# 21_CAN.net
KiCad netlist of a schematic drawn in Altium Designer
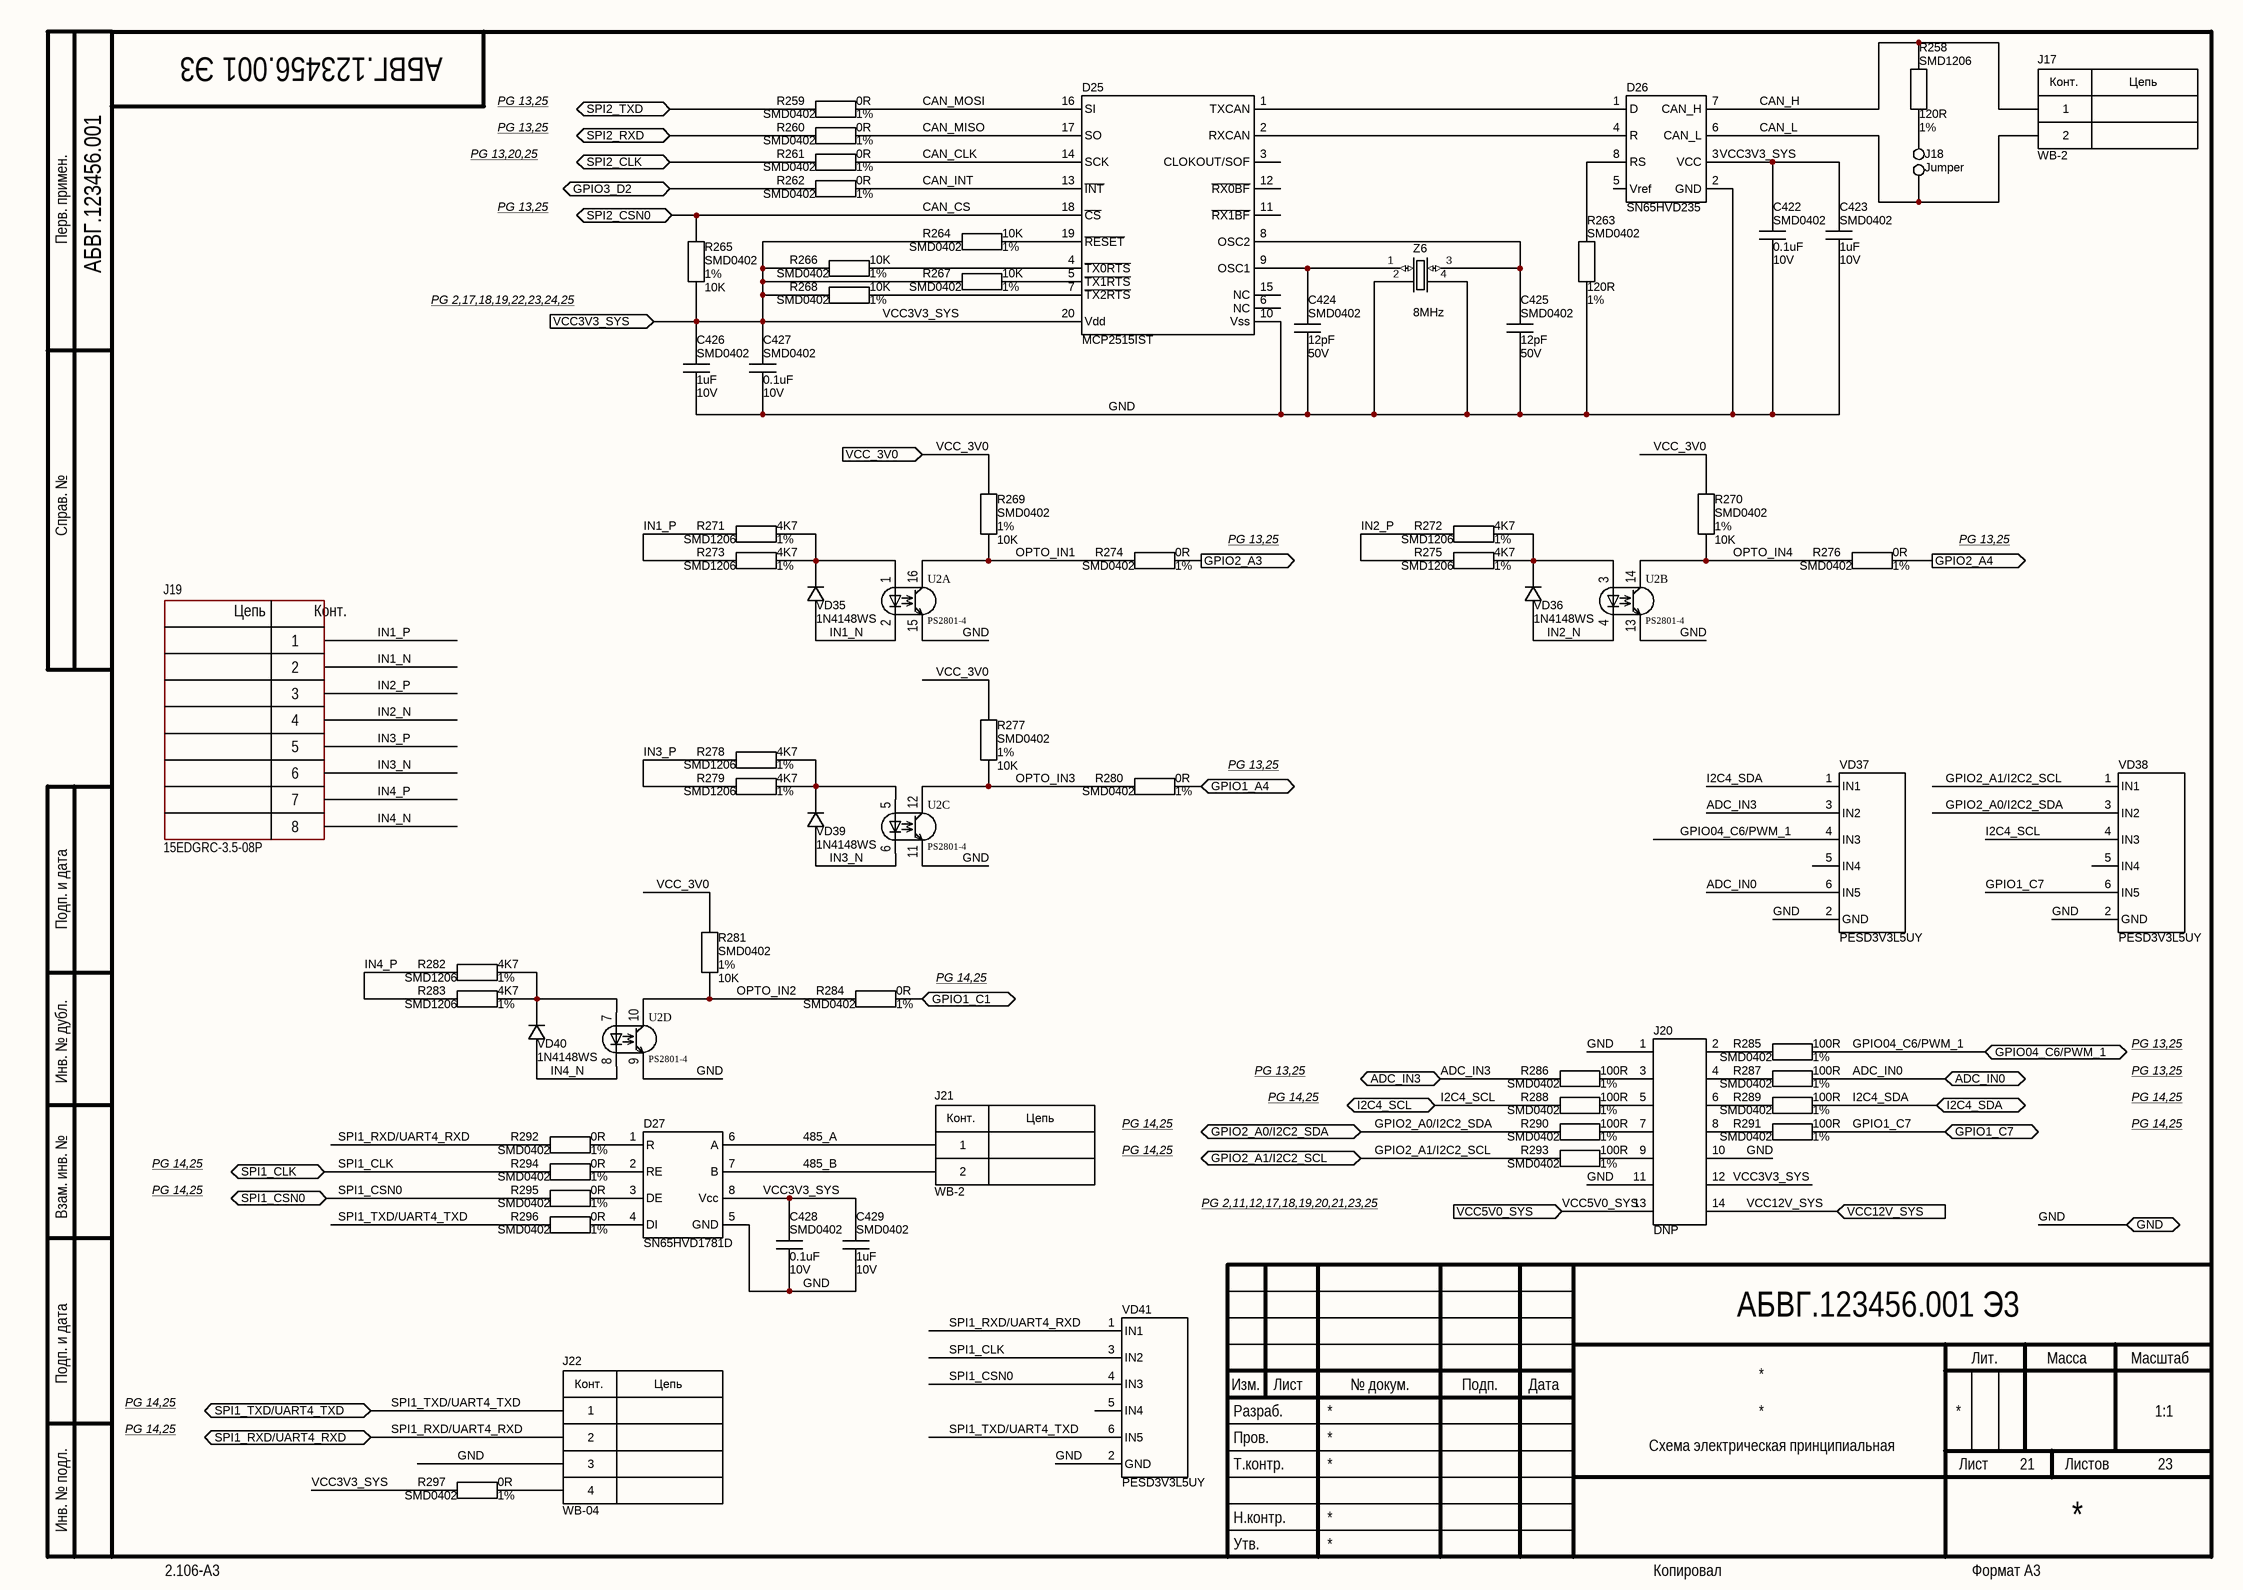
[diagram p0: 21 CAN.SchDoc]

(export (version "E")
  (design (tool "Eeschema 10.0.6"))
  (components
    (comp (ref "C422")
      (value "0.1uF")
      (footprint "Didur_PcbLib_1:CAP_SMD_0402")
      (fields
        (field (name "PACKAGE") "SMD0402")
        (field (name "PARTNUMBER") "CC0402KRX5R6BB104")
        (field (name "VOLTAGE") "10V")
      )
      (libsource (lib "Didur_SchLib_1") (part "Ceramic_Cap"))
    )
    (comp (ref "C423")
      (value "1uF")
      (footprint "Didur_PcbLib_1:CAP_SMD_0402")
      (fields
        (field (name "PACKAGE") "SMD0402")
        (field (name "PARTNUMBER") "CC0402KRX5R6BB105")
        (field (name "VOLTAGE") "10V")
      )
      (libsource (lib "Didur_SchLib_1") (part "Ceramic_Cap"))
    )
    (comp (ref "C424")
      (value "12pF")
      (footprint "Didur_PcbLib_1:CAP_SMD_0402")
      (fields
        (field (name "PACKAGE") "SMD0402")
        (field (name "PARTNUMBER") "CC0402JRNPO9BN120")
        (field (name "VOLTAGE") "50V")
      )
      (libsource (lib "Didur_SchLib_1") (part "Ceramic_Cap"))
    )
    (comp (ref "C425")
      (value "12pF")
      (footprint "Didur_PcbLib_1:CAP_SMD_0402")
      (fields
        (field (name "PACKAGE") "SMD0402")
        (field (name "PARTNUMBER") "CC0402JRNPO9BN120")
        (field (name "VOLTAGE") "50V")
      )
      (libsource (lib "Didur_SchLib_1") (part "Ceramic_Cap"))
    )
    (comp (ref "C426")
      (value "1uF")
      (footprint "Didur_PcbLib_1:CAP_SMD_0402")
      (fields
        (field (name "PACKAGE") "SMD0402")
        (field (name "PARTNUMBER") "CC0402KRX5R6BB105")
        (field (name "VOLTAGE") "10V")
      )
      (libsource (lib "Didur_SchLib_1") (part "Ceramic_Cap"))
    )
    (comp (ref "C427")
      (value "0.1uF")
      (footprint "Didur_PcbLib_1:CAP_SMD_0402")
      (fields
        (field (name "PACKAGE") "SMD0402")
        (field (name "PARTNUMBER") "CC0402KRX5R6BB104")
        (field (name "VOLTAGE") "10V")
      )
      (libsource (lib "Didur_SchLib_1") (part "Ceramic_Cap"))
    )
    (comp (ref "C428")
      (value "0.1uF")
      (footprint "Didur_PcbLib_1:CAP_SMD_0402")
      (fields
        (field (name "PACKAGE") "SMD0402")
        (field (name "PARTNUMBER") "CC0402KRX5R6BB104")
        (field (name "VOLTAGE") "10V")
      )
      (libsource (lib "Didur_SchLib_1") (part "Ceramic_Cap"))
    )
    (comp (ref "C429")
      (value "1uF")
      (footprint "Didur_PcbLib_1:CAP_SMD_0402")
      (fields
        (field (name "PACKAGE") "SMD0402")
        (field (name "PARTNUMBER") "CC0402KRX5R6BB105")
        (field (name "VOLTAGE") "10V")
      )
      (libsource (lib "Didur_SchLib_1") (part "Ceramic_Cap"))
    )
    (comp (ref "D25")
      (value "MCP2515IST")
      (footprint "Didur_PcbLib_1:TSSOP-20")
      (libsource (lib "Didur_SchLib_1") (part "MCP2515IST"))
    )
    (comp (ref "D26")
      (value "SN65HVD235")
      (footprint "SO8")
      (fields (field (name "PARTNUMBER") "SN65HVD235D"))
      (libsource (lib "Didur_SchLib_1") (part "SN65HVD230D"))
    )
    (comp (ref "D27")
      (value "SN65HVD1781D")
      (footprint "SO8")
      (libsource (lib "Didur_SchLib_1") (part "SN65HVD1781D"))
    )
    (comp (ref "J17")
      (value "WB-2")
      (footprint "Didur_PcbLib_1:15EDGRC-3.5-02P")
      (fields (field (name "PARTNUMBER") "DS1066-02M(MW-2M)"))
      (libsource (lib "Didur_SchLib_1") (part "CON2"))
    )
    (comp (ref "J18")
      (value "Jumper")
      (footprint "Didur_PcbLib_1:Jumper2")
      (fields (field (name "PARTNUMBER") "DS1025-01-1x2P8BV1-B"))
      (libsource (lib "Didur_SchLib_1") (part "Jumper"))
    )
    (comp (ref "J19")
      (value "15EDGRC-3.5-08P")
      (footprint "Didur_PcbLib_1:15EDGRC-3.5-08P")
      (libsource (lib "Didur_SchLib_1") (part "CON8"))
    )
    (comp (ref "J20")
      (value "DNP")
      (footprint "Didur_PcbLib_1:PLD2-14 (2.00)")
      (fields (field (name "PARTNUMBER") "PLD2-14 (2.00"))
      (libsource (lib "Didur_SchLib_1") (part "CON14_2"))
    )
    (comp (ref "J21")
      (value "WB-2")
      (footprint "Didur_PcbLib_1:15EDGRC-3.5-02P")
      (fields (field (name "PARTNUMBER") "DS1066-02M(MW-2M)"))
      (libsource (lib "Didur_SchLib_1") (part "CON2"))
    )
    (comp (ref "J22")
      (value "WB-04")
      (footprint "Didur_PcbLib_1:WB-4")
      (fields (field (name "PARTNUMBER") "DS1066-04M"))
      (libsource (lib "Didur_SchLib_1") (part "CON4"))
    )
    (comp (ref "R258")
      (value "120R")
      (footprint "RES_SMD_1206")
      (fields
        (field (name "PACKAGE") "SMD1206")
        (field (name "PARTNUMBER") "RC1206FR-07120RL")
        (field (name "TOLERANCE") "1%")
      )
      (libsource (lib "") (part "Chip_Res_1"))
    )
    (comp (ref "R259")
      (value "0R")
      (footprint "Didur_PcbLib_1:RES_SMD_0402")
      (fields
        (field (name "PACKAGE") "SMD0402")
        (field (name "PARTNUMBER") "RC0402FR-070RL")
        (field (name "TOLERANCE") "1%")
      )
      (libsource (lib "Didur_SchLib_1") (part "Chip_Res"))
    )
    (comp (ref "R260")
      (value "0R")
      (footprint "Didur_PcbLib_1:RES_SMD_0402")
      (fields
        (field (name "PACKAGE") "SMD0402")
        (field (name "PARTNUMBER") "RC0402FR-070RL")
        (field (name "TOLERANCE") "1%")
      )
      (libsource (lib "Didur_SchLib_1") (part "Chip_Res"))
    )
    (comp (ref "R261")
      (value "0R")
      (footprint "Didur_PcbLib_1:RES_SMD_0402")
      (fields
        (field (name "PACKAGE") "SMD0402")
        (field (name "PARTNUMBER") "RC0402FR-070RL")
        (field (name "TOLERANCE") "1%")
      )
      (libsource (lib "Didur_SchLib_1") (part "Chip_Res"))
    )
    (comp (ref "R262")
      (value "0R")
      (footprint "Didur_PcbLib_1:RES_SMD_0402")
      (fields
        (field (name "PACKAGE") "SMD0402")
        (field (name "PARTNUMBER") "RC0402FR-070RL")
        (field (name "TOLERANCE") "1%")
      )
      (libsource (lib "Didur_SchLib_1") (part "Chip_Res"))
    )
    (comp (ref "R263")
      (value "120R")
      (footprint "Didur_PcbLib_1:RES_SMD_0402")
      (fields
        (field (name "PACKAGE") "SMD0402")
        (field (name "PARTNUMBER") "RC0402FR-07120RL")
        (field (name "TOLERANCE") "1%")
      )
      (libsource (lib "") (part "Chip_Res_1"))
    )
    (comp (ref "R264")
      (value "10K")
      (footprint "Didur_PcbLib_1:RES_SMD_0402")
      (fields
        (field (name "PACKAGE") "SMD0402")
        (field (name "PARTNUMBER") "RC0402FR-0710KL")
        (field (name "TOLERANCE") "1%")
      )
      (libsource (lib "") (part "Chip_Res_2"))
    )
    (comp (ref "R265")
      (value "10K")
      (footprint "Didur_PcbLib_1:RES_SMD_0402")
      (fields
        (field (name "PACKAGE") "SMD0402")
        (field (name "PARTNUMBER") "RC0402FR-0710KL")
        (field (name "TOLERANCE") "1%")
      )
      (libsource (lib "") (part "Chip_Res_3"))
    )
    (comp (ref "R266")
      (value "10K")
      (footprint "Didur_PcbLib_1:RES_SMD_0402")
      (fields
        (field (name "PACKAGE") "SMD0402")
        (field (name "PARTNUMBER") "RC0402FR-0710KL")
        (field (name "TOLERANCE") "1%")
      )
      (libsource (lib "") (part "Chip_Res_2"))
    )
    (comp (ref "R267")
      (value "10K")
      (footprint "Didur_PcbLib_1:RES_SMD_0402")
      (fields
        (field (name "PACKAGE") "SMD0402")
        (field (name "PARTNUMBER") "RC0402FR-0710KL")
        (field (name "TOLERANCE") "1%")
      )
      (libsource (lib "") (part "Chip_Res_2"))
    )
    (comp (ref "R268")
      (value "10K")
      (footprint "Didur_PcbLib_1:RES_SMD_0402")
      (fields
        (field (name "PACKAGE") "SMD0402")
        (field (name "PARTNUMBER") "RC0402FR-0710KL")
        (field (name "TOLERANCE") "1%")
      )
      (libsource (lib "") (part "Chip_Res_2"))
    )
    (comp (ref "R269")
      (value "10K")
      (footprint "Didur_PcbLib_1:RES_SMD_0402")
      (fields
        (field (name "PACKAGE") "SMD0402")
        (field (name "PARTNUMBER") "RC0402FR-0710KL")
        (field (name "TOLERANCE") "1%")
      )
      (libsource (lib "") (part "Chip_Res_3"))
    )
    (comp (ref "R270")
      (value "10K")
      (footprint "Didur_PcbLib_1:RES_SMD_0402")
      (fields
        (field (name "PACKAGE") "SMD0402")
        (field (name "PARTNUMBER") "RC0402FR-0710KL")
        (field (name "TOLERANCE") "1%")
      )
      (libsource (lib "") (part "Chip_Res_3"))
    )
    (comp (ref "R271")
      (value "4K7")
      (footprint "RES_SMD_1206")
      (fields
        (field (name "PACKAGE") "SMD1206")
        (field (name "PARTNUMBER") "RC1206FR-074K7L")
        (field (name "TOLERANCE") "1%")
      )
      (libsource (lib "") (part "Chip_Res_2"))
    )
    (comp (ref "R272")
      (value "4K7")
      (footprint "RES_SMD_1206")
      (fields
        (field (name "PACKAGE") "SMD1206")
        (field (name "PARTNUMBER") "RC1206FR-074K7L")
        (field (name "TOLERANCE") "1%")
      )
      (libsource (lib "") (part "Chip_Res_2"))
    )
    (comp (ref "R273")
      (value "4K7")
      (footprint "RES_SMD_1206")
      (fields
        (field (name "PACKAGE") "SMD1206")
        (field (name "PARTNUMBER") "RC1206FR-074K7L")
        (field (name "TOLERANCE") "1%")
      )
      (libsource (lib "") (part "Chip_Res_2"))
    )
    (comp (ref "R274")
      (value "0R")
      (footprint "Didur_PcbLib_1:RES_SMD_0402")
      (fields
        (field (name "PACKAGE") "SMD0402")
        (field (name "PARTNUMBER") "RC0402FR-070RL")
        (field (name "TOLERANCE") "1%")
      )
      (libsource (lib "Didur_SchLib_1") (part "Chip_Res"))
    )
    (comp (ref "R275")
      (value "4K7")
      (footprint "RES_SMD_1206")
      (fields
        (field (name "PACKAGE") "SMD1206")
        (field (name "PARTNUMBER") "RC1206FR-074K7L")
        (field (name "TOLERANCE") "1%")
      )
      (libsource (lib "") (part "Chip_Res_2"))
    )
    (comp (ref "R276")
      (value "0R")
      (footprint "Didur_PcbLib_1:RES_SMD_0402")
      (fields
        (field (name "PACKAGE") "SMD0402")
        (field (name "PARTNUMBER") "RC0402FR-070RL")
        (field (name "TOLERANCE") "1%")
      )
      (libsource (lib "Didur_SchLib_1") (part "Chip_Res"))
    )
    (comp (ref "R277")
      (value "10K")
      (footprint "Didur_PcbLib_1:RES_SMD_0402")
      (fields
        (field (name "PACKAGE") "SMD0402")
        (field (name "PARTNUMBER") "RC0402FR-0710KL")
        (field (name "TOLERANCE") "1%")
      )
      (libsource (lib "") (part "Chip_Res_3"))
    )
    (comp (ref "R278")
      (value "4K7")
      (footprint "RES_SMD_1206")
      (fields
        (field (name "PACKAGE") "SMD1206")
        (field (name "PARTNUMBER") "RC1206FR-074K7L")
        (field (name "TOLERANCE") "1%")
      )
      (libsource (lib "") (part "Chip_Res_2"))
    )
    (comp (ref "R279")
      (value "4K7")
      (footprint "RES_SMD_1206")
      (fields
        (field (name "PACKAGE") "SMD1206")
        (field (name "PARTNUMBER") "RC1206FR-074K7L")
        (field (name "TOLERANCE") "1%")
      )
      (libsource (lib "") (part "Chip_Res_2"))
    )
    (comp (ref "R280")
      (value "0R")
      (footprint "Didur_PcbLib_1:RES_SMD_0402")
      (fields
        (field (name "PACKAGE") "SMD0402")
        (field (name "PARTNUMBER") "RC0402FR-070RL")
        (field (name "TOLERANCE") "1%")
      )
      (libsource (lib "Didur_SchLib_1") (part "Chip_Res"))
    )
    (comp (ref "R281")
      (value "10K")
      (footprint "Didur_PcbLib_1:RES_SMD_0402")
      (fields
        (field (name "PACKAGE") "SMD0402")
        (field (name "PARTNUMBER") "RC0402FR-0710KL")
        (field (name "TOLERANCE") "1%")
      )
      (libsource (lib "") (part "Chip_Res_3"))
    )
    (comp (ref "R282")
      (value "4K7")
      (footprint "RES_SMD_1206")
      (fields
        (field (name "PACKAGE") "SMD1206")
        (field (name "PARTNUMBER") "RC1206FR-074K7L")
        (field (name "TOLERANCE") "1%")
      )
      (libsource (lib "") (part "Chip_Res_2"))
    )
    (comp (ref "R283")
      (value "4K7")
      (footprint "RES_SMD_1206")
      (fields
        (field (name "PACKAGE") "SMD1206")
        (field (name "PARTNUMBER") "RC1206FR-074K7L")
        (field (name "TOLERANCE") "1%")
      )
      (libsource (lib "") (part "Chip_Res_2"))
    )
    (comp (ref "R284")
      (value "0R")
      (footprint "Didur_PcbLib_1:RES_SMD_0402")
      (fields
        (field (name "PACKAGE") "SMD0402")
        (field (name "PARTNUMBER") "RC0402FR-070RL")
        (field (name "TOLERANCE") "1%")
      )
      (libsource (lib "Didur_SchLib_1") (part "Chip_Res"))
    )
    (comp (ref "R285")
      (value "100R")
      (footprint "Didur_PcbLib_1:RES_SMD_0402")
      (fields
        (field (name "PACKAGE") "SMD0402")
        (field (name "PARTNUMBER") "RC0402FR-07100RL")
        (field (name "TOLERANCE") "1%")
      )
      (libsource (lib "Didur_SchLib_1") (part "Chip_Res"))
    )
    (comp (ref "R286")
      (value "100R")
      (footprint "Didur_PcbLib_1:RES_SMD_0402")
      (fields
        (field (name "PACKAGE") "SMD0402")
        (field (name "PARTNUMBER") "RC0402FR-07100RL")
        (field (name "TOLERANCE") "1%")
      )
      (libsource (lib "Didur_SchLib_1") (part "Chip_Res"))
    )
    (comp (ref "R287")
      (value "100R")
      (footprint "Didur_PcbLib_1:RES_SMD_0402")
      (fields
        (field (name "PACKAGE") "SMD0402")
        (field (name "PARTNUMBER") "RC0402FR-07100RL")
        (field (name "TOLERANCE") "1%")
      )
      (libsource (lib "Didur_SchLib_1") (part "Chip_Res"))
    )
    (comp (ref "R288")
      (value "100R")
      (footprint "Didur_PcbLib_1:RES_SMD_0402")
      (fields
        (field (name "PACKAGE") "SMD0402")
        (field (name "PARTNUMBER") "RC0402FR-07100RL")
        (field (name "TOLERANCE") "1%")
      )
      (libsource (lib "Didur_SchLib_1") (part "Chip_Res"))
    )
    (comp (ref "R289")
      (value "100R")
      (footprint "Didur_PcbLib_1:RES_SMD_0402")
      (fields
        (field (name "PACKAGE") "SMD0402")
        (field (name "PARTNUMBER") "RC0402FR-07100RL")
        (field (name "TOLERANCE") "1%")
      )
      (libsource (lib "Didur_SchLib_1") (part "Chip_Res"))
    )
    (comp (ref "R290")
      (value "100R")
      (footprint "Didur_PcbLib_1:RES_SMD_0402")
      (fields
        (field (name "PACKAGE") "SMD0402")
        (field (name "PARTNUMBER") "RC0402FR-07100RL")
        (field (name "TOLERANCE") "1%")
      )
      (libsource (lib "Didur_SchLib_1") (part "Chip_Res"))
    )
    (comp (ref "R291")
      (value "100R")
      (footprint "Didur_PcbLib_1:RES_SMD_0402")
      (fields
        (field (name "PACKAGE") "SMD0402")
        (field (name "PARTNUMBER") "RC0402FR-07100RL")
        (field (name "TOLERANCE") "1%")
      )
      (libsource (lib "Didur_SchLib_1") (part "Chip_Res"))
    )
    (comp (ref "R292")
      (value "0R")
      (footprint "Didur_PcbLib_1:RES_SMD_0402")
      (fields
        (field (name "PACKAGE") "SMD0402")
        (field (name "PARTNUMBER") "RC0402FR-070RL")
        (field (name "TOLERANCE") "1%")
      )
      (libsource (lib "Didur_SchLib_1") (part "Chip_Res"))
    )
    (comp (ref "R293")
      (value "100R")
      (footprint "Didur_PcbLib_1:RES_SMD_0402")
      (fields
        (field (name "PACKAGE") "SMD0402")
        (field (name "PARTNUMBER") "RC0402FR-07100RL")
        (field (name "TOLERANCE") "1%")
      )
      (libsource (lib "Didur_SchLib_1") (part "Chip_Res"))
    )
    (comp (ref "R294")
      (value "0R")
      (footprint "Didur_PcbLib_1:RES_SMD_0402")
      (fields
        (field (name "PACKAGE") "SMD0402")
        (field (name "PARTNUMBER") "RC0402FR-070RL")
        (field (name "TOLERANCE") "1%")
      )
      (libsource (lib "Didur_SchLib_1") (part "Chip_Res"))
    )
    (comp (ref "R295")
      (value "0R")
      (footprint "Didur_PcbLib_1:RES_SMD_0402")
      (fields
        (field (name "PACKAGE") "SMD0402")
        (field (name "PARTNUMBER") "RC0402FR-070RL")
        (field (name "TOLERANCE") "1%")
      )
      (libsource (lib "Didur_SchLib_1") (part "Chip_Res"))
    )
    (comp (ref "R296")
      (value "0R")
      (footprint "Didur_PcbLib_1:RES_SMD_0402")
      (fields
        (field (name "PACKAGE") "SMD0402")
        (field (name "PARTNUMBER") "RC0402FR-070RL")
        (field (name "TOLERANCE") "1%")
      )
      (libsource (lib "Didur_SchLib_1") (part "Chip_Res"))
    )
    (comp (ref "R297")
      (value "0R")
      (footprint "Didur_PcbLib_1:RES_SMD_0402")
      (fields
        (field (name "PACKAGE") "SMD0402")
        (field (name "PARTNUMBER") "RC0402FR-070RL")
        (field (name "TOLERANCE") "1%")
      )
      (libsource (lib "Didur_SchLib_1") (part "Chip_Res"))
    )
    (comp (ref "U2")
      (value "PS2801-4")
      (footprint "SOIC127P700X210-16N")
      (description "Optocoupler X4")
      (fields (field (name "MANUFACTURER") "Renesas") (field (name "PARTNUMBER") "PS2801-4-F3-A"))
      (libsource (lib "Didur_SchLib_1") (part "PS2801-4-F3-A"))
    )
    (comp (ref "VD35")
      (value "1N4148WS")
      (footprint "SOD323")
      (fields (field (name "Comment") "Diode"))
      (libsource (lib "Didur_SchLib_1") (part "Diode"))
    )
    (comp (ref "VD36")
      (value "1N4148WS")
      (footprint "SOD323")
      (fields (field (name "Comment") "Diode"))
      (libsource (lib "Didur_SchLib_1") (part "Diode"))
    )
    (comp (ref "VD37")
      (value "PESD3V3L5UY")
      (footprint "Didur_PcbLib_1:SC70-6")
      (libsource (lib "Didur_SchLib_1") (part "PESD3V3L5UY"))
    )
    (comp (ref "VD38")
      (value "PESD3V3L5UY")
      (footprint "Didur_PcbLib_1:SC70-6")
      (libsource (lib "Didur_SchLib_1") (part "PESD3V3L5UY"))
    )
    (comp (ref "VD39")
      (value "1N4148WS")
      (footprint "SOD323")
      (fields (field (name "Comment") "Diode"))
      (libsource (lib "Didur_SchLib_1") (part "Diode"))
    )
    (comp (ref "VD40")
      (value "1N4148WS")
      (footprint "SOD323")
      (fields (field (name "Comment") "Diode"))
      (libsource (lib "Didur_SchLib_1") (part "Diode"))
    )
    (comp (ref "VD41")
      (value "PESD3V3L5UY")
      (footprint "Didur_PcbLib_1:SC70-6")
      (libsource (lib "Didur_SchLib_1") (part "PESD3V3L5UY"))
    )
    (comp (ref "Z6")
      (value "8MHz")
      (footprint "Didur_PcbLib_1:TSX3225")
      (fields (field (name "PARTNUMBER") "X32258MOB4SI") (field (name "Comment") "Value"))
      (libsource (lib "Didur_SchLib_1") (part "OSC3225"))
    )
  )
  (nets
    (net (code "1") (name "/485_A") (class "Default")
      (node (ref "D27") (pin "6") (pinfunction "A_6") (pintype "passive"))
      (node (ref "J21") (pin "1") (pinfunction "1_1") (pintype "passive"))
    )
    (net (code "2") (name "/485_B") (class "Default")
      (node (ref "D27") (pin "7") (pinfunction "B_7") (pintype "passive"))
      (node (ref "J21") (pin "2") (pinfunction "2_2") (pintype "passive"))
    )
    (net (code "3") (name "/ADC_IN0") (class "Default")
      (node (ref "R287") (pin "2") (pinfunction "2_2") (pintype "passive"))
      (node (ref "VD37") (pin "6") (pinfunction "IN5_6") (pintype "passive"))
    )
    (net (code "4") (name "/ADC_IN3") (class "Default")
      (node (ref "R286") (pin "1") (pinfunction "1_1") (pintype "passive"))
      (node (ref "VD37") (pin "3") (pinfunction "IN2_3") (pintype "passive"))
    )
    (net (code "5") (name "/CAN_CLK") (class "Default")
      (node (ref "D25") (pin "14") (pinfunction "SCK_14") (pintype "passive"))
      (node (ref "R261") (pin "2") (pinfunction "2_2") (pintype "passive"))
    )
    (net (code "6") (name "/CAN_CS") (class "Default")
      (node (ref "D25") (pin "18") (pinfunction "~{CS}_18") (pintype "passive"))
      (node (ref "R265") (pin "2") (pinfunction "2_2") (pintype "passive"))
    )
    (net (code "7") (name "/CAN_H") (class "Default")
      (node (ref "D26") (pin "7") (pinfunction "CAN_H_7") (pintype "passive"))
      (node (ref "J17") (pin "1") (pinfunction "1_1") (pintype "passive"))
      (node (ref "R258") (pin "1") (pinfunction "1_1") (pintype "passive"))
    )
    (net (code "8") (name "/CAN_INT") (class "Default")
      (node (ref "D25") (pin "13") (pinfunction "~{INT}_13") (pintype "passive"))
      (node (ref "R262") (pin "2") (pinfunction "2_2") (pintype "passive"))
    )
    (net (code "9") (name "/CAN_L") (class "Default")
      (node (ref "D26") (pin "6") (pinfunction "CAN_L_6") (pintype "passive"))
      (node (ref "J17") (pin "2") (pinfunction "2_2") (pintype "passive"))
      (node (ref "J18") (pin "1") (pinfunction "1_1") (pintype "passive"))
    )
    (net (code "10") (name "/CAN_MISO") (class "Default")
      (node (ref "D25") (pin "17") (pinfunction "SO_17") (pintype "passive"))
      (node (ref "R260") (pin "2") (pinfunction "2_2") (pintype "passive"))
    )
    (net (code "11") (name "/CAN_MOSI") (class "Default")
      (node (ref "D25") (pin "16") (pinfunction "SI_16") (pintype "passive"))
      (node (ref "R259") (pin "2") (pinfunction "2_2") (pintype "passive"))
    )
    (net (code "12") (name "/GND") (class "Default")
      (node (ref "C422") (pin "2") (pinfunction "2_2") (pintype "power_in"))
      (node (ref "C423") (pin "2") (pinfunction "2_2") (pintype "power_in"))
      (node (ref "C424") (pin "2") (pinfunction "2_2") (pintype "power_in"))
      (node (ref "C425") (pin "2") (pinfunction "2_2") (pintype "power_in"))
      (node (ref "C426") (pin "2") (pinfunction "2_2") (pintype "power_in"))
      (node (ref "C427") (pin "2") (pinfunction "2_2") (pintype "power_in"))
      (node (ref "C428") (pin "2") (pinfunction "2_2") (pintype "power_in"))
      (node (ref "C429") (pin "2") (pinfunction "2_2") (pintype "power_in"))
      (node (ref "D25") (pin "10") (pinfunction "Vss_10") (pintype "passive"))
      (node (ref "D26") (pin "2") (pinfunction "GND_2") (pintype "passive"))
      (node (ref "D27") (pin "5") (pinfunction "GND_5") (pintype "passive"))
      (node (ref "J20") (pin "1") (pinfunction "1_1") (pintype "passive"))
      (node (ref "J20") (pin "10") (pinfunction "10_10") (pintype "passive"))
      (node (ref "J20") (pin "11") (pinfunction "11_11") (pintype "passive"))
      (node (ref "J22") (pin "3") (pinfunction "3_3") (pintype "power_in"))
      (node (ref "R263") (pin "2") (pinfunction "2_2") (pintype "passive"))
      (node (ref "U2") (pin "11") (pinfunction "E_11") (pintype "passive"))
      (node (ref "U2") (pin "13") (pinfunction "E_13") (pintype "passive"))
      (node (ref "U2") (pin "15") (pinfunction "E_15") (pintype "passive"))
      (node (ref "U2") (pin "9") (pinfunction "E_9") (pintype "passive"))
      (node (ref "VD37") (pin "2") (pinfunction "GND_2") (pintype "passive"))
      (node (ref "VD38") (pin "2") (pinfunction "GND_2") (pintype "passive"))
      (node (ref "VD41") (pin "2") (pinfunction "GND_2") (pintype "passive"))
      (node (ref "Z6") (pin "2") (pinfunction "GND_2") (pintype "passive"))
      (node (ref "Z6") (pin "4") (pinfunction "GND_4") (pintype "passive"))
    )
    (net (code "13") (name "/GPIO1_A4") (class "Default")
      (node (ref "R280") (pin "2") (pinfunction "2_2") (pintype "passive"))
    )
    (net (code "14") (name "/GPIO1_C1") (class "Default")
      (node (ref "R284") (pin "2") (pinfunction "2_2") (pintype "passive"))
    )
    (net (code "15") (name "/GPIO1_C7") (class "Default")
      (node (ref "R291") (pin "2") (pinfunction "2_2") (pintype "passive"))
      (node (ref "VD38") (pin "6") (pinfunction "IN5_6") (pintype "passive"))
    )
    (net (code "16") (name "/GPIO2_A0{slash}I2C2_SDA") (class "Default")
      (node (ref "R290") (pin "1") (pinfunction "1_1") (pintype "passive"))
      (node (ref "VD38") (pin "3") (pinfunction "IN2_3") (pintype "passive"))
    )
    (net (code "17") (name "/GPIO2_A1{slash}I2C2_SCL") (class "Default")
      (node (ref "R293") (pin "1") (pinfunction "1_1") (pintype "passive"))
      (node (ref "VD38") (pin "1") (pinfunction "IN1_1") (pintype "passive"))
    )
    (net (code "18") (name "/GPIO2_A3") (class "Default")
      (node (ref "R274") (pin "2") (pinfunction "2_2") (pintype "passive"))
    )
    (net (code "19") (name "/GPIO2_A4") (class "Default")
      (node (ref "R276") (pin "2") (pinfunction "2_2") (pintype "passive"))
    )
    (net (code "20") (name "/GPIO3_D2") (class "Default")
      (node (ref "R262") (pin "1") (pinfunction "1_1") (pintype "passive"))
    )
    (net (code "21") (name "/GPIO04_C6{slash}PWM_1") (class "Default")
      (node (ref "R285") (pin "2") (pinfunction "2_2") (pintype "passive"))
      (node (ref "VD37") (pin "4") (pinfunction "IN3_4") (pintype "passive"))
    )
    (net (code "22") (name "/I2C4_SCL") (class "Default")
      (node (ref "R288") (pin "1") (pinfunction "1_1") (pintype "passive"))
      (node (ref "VD38") (pin "4") (pinfunction "IN3_4") (pintype "passive"))
    )
    (net (code "23") (name "/I2C4_SDA") (class "Default")
      (node (ref "R289") (pin "2") (pinfunction "2_2") (pintype "passive"))
      (node (ref "VD37") (pin "1") (pinfunction "IN1_1") (pintype "passive"))
    )
    (net (code "24") (name "/IN1_N") (class "Default")
      (node (ref "J19") (pin "2") (pinfunction "2_2") (pintype "passive"))
      (node (ref "U2") (pin "2") (pinfunction "C_2") (pintype "passive"))
      (node (ref "VD35") (pin "1") (pinfunction "A_1") (pintype "passive"))
    )
    (net (code "25") (name "/IN1_P") (class "Default")
      (node (ref "J19") (pin "1") (pinfunction "1_1") (pintype "passive"))
      (node (ref "R271") (pin "2") (pinfunction "2_2") (pintype "passive"))
      (node (ref "R273") (pin "2") (pinfunction "2_2") (pintype "passive"))
    )
    (net (code "26") (name "/IN2_N") (class "Default")
      (node (ref "J19") (pin "4") (pinfunction "4_4") (pintype "power_in"))
      (node (ref "U2") (pin "4") (pinfunction "C_4") (pintype "passive"))
      (node (ref "VD36") (pin "1") (pinfunction "A_1") (pintype "passive"))
    )
    (net (code "27") (name "/IN2_P") (class "Default")
      (node (ref "J19") (pin "3") (pinfunction "3_3") (pintype "power_in"))
      (node (ref "R272") (pin "2") (pinfunction "2_2") (pintype "passive"))
      (node (ref "R275") (pin "2") (pinfunction "2_2") (pintype "passive"))
    )
    (net (code "28") (name "/IN3_N") (class "Default")
      (node (ref "J19") (pin "6") (pinfunction "6_6") (pintype "power_in"))
      (node (ref "U2") (pin "6") (pinfunction "C_6") (pintype "passive"))
      (node (ref "VD39") (pin "1") (pinfunction "A_1") (pintype "passive"))
    )
    (net (code "29") (name "/IN3_P") (class "Default")
      (node (ref "J19") (pin "5") (pinfunction "5_5") (pintype "power_in"))
      (node (ref "R278") (pin "2") (pinfunction "2_2") (pintype "passive"))
      (node (ref "R279") (pin "2") (pinfunction "2_2") (pintype "passive"))
    )
    (net (code "30") (name "/IN4_N") (class "Default")
      (node (ref "J19") (pin "8") (pinfunction "8_8") (pintype "power_in"))
      (node (ref "U2") (pin "8") (pinfunction "C_8") (pintype "passive"))
      (node (ref "VD40") (pin "1") (pinfunction "A_1") (pintype "passive"))
    )
    (net (code "31") (name "/IN4_P") (class "Default")
      (node (ref "J19") (pin "7") (pinfunction "7_7") (pintype "power_in"))
      (node (ref "R282") (pin "2") (pinfunction "2_2") (pintype "passive"))
      (node (ref "R283") (pin "2") (pinfunction "2_2") (pintype "passive"))
    )
    (net (code "32") (name "/OPTO_IN1") (class "Default")
      (node (ref "R269") (pin "1") (pinfunction "1_1") (pintype "passive"))
      (node (ref "R274") (pin "1") (pinfunction "1_1") (pintype "passive"))
      (node (ref "U2") (pin "16") (pinfunction "C_16") (pintype "passive"))
    )
    (net (code "33") (name "/OPTO_IN2") (class "Default")
      (node (ref "R281") (pin "1") (pinfunction "1_1") (pintype "passive"))
      (node (ref "R284") (pin "1") (pinfunction "1_1") (pintype "passive"))
      (node (ref "U2") (pin "10") (pinfunction "C_10") (pintype "passive"))
    )
    (net (code "34") (name "/OPTO_IN3") (class "Default")
      (node (ref "R277") (pin "1") (pinfunction "1_1") (pintype "passive"))
      (node (ref "R280") (pin "1") (pinfunction "1_1") (pintype "passive"))
      (node (ref "U2") (pin "12") (pinfunction "C_12") (pintype "passive"))
    )
    (net (code "35") (name "/OPTO_IN4") (class "Default")
      (node (ref "R270") (pin "1") (pinfunction "1_1") (pintype "passive"))
      (node (ref "R276") (pin "1") (pinfunction "1_1") (pintype "passive"))
      (node (ref "U2") (pin "14") (pinfunction "C_14") (pintype "passive"))
    )
    (net (code "36") (name "/SPI1_CLK") (class "Default")
      (node (ref "R294") (pin "1") (pinfunction "1_1") (pintype "passive"))
      (node (ref "VD41") (pin "3") (pinfunction "IN2_3") (pintype "passive"))
    )
    (net (code "37") (name "/SPI1_CSN0") (class "Default")
      (node (ref "R295") (pin "1") (pinfunction "1_1") (pintype "passive"))
      (node (ref "VD41") (pin "4") (pinfunction "IN3_4") (pintype "passive"))
    )
    (net (code "38") (name "/SPI1_RXD{slash}UART4_RXD") (class "Default")
      (node (ref "J22") (pin "2") (pinfunction "2_2") (pintype "passive"))
      (node (ref "R292") (pin "1") (pinfunction "1_1") (pintype "passive"))
      (node (ref "VD41") (pin "1") (pinfunction "IN1_1") (pintype "passive"))
    )
    (net (code "39") (name "/SPI1_TXD{slash}UART4_TXD") (class "Default")
      (node (ref "J22") (pin "1") (pinfunction "1_1") (pintype "passive"))
      (node (ref "R296") (pin "1") (pinfunction "1_1") (pintype "passive"))
      (node (ref "VD41") (pin "6") (pinfunction "IN5_6") (pintype "passive"))
    )
    (net (code "40") (name "/SPI2_CLK") (class "Default")
      (node (ref "R261") (pin "1") (pinfunction "1_1") (pintype "passive"))
    )
    (net (code "41") (name "/SPI2_RXD") (class "Default")
      (node (ref "R260") (pin "1") (pinfunction "1_1") (pintype "passive"))
    )
    (net (code "42") (name "/SPI2_TXD") (class "Default")
      (node (ref "R259") (pin "1") (pinfunction "1_1") (pintype "passive"))
    )
    (net (code "43") (name "/VCC3V3_SYS") (class "Default")
      (node (ref "C422") (pin "1") (pinfunction "1_1") (pintype "power_in"))
      (node (ref "C423") (pin "1") (pinfunction "1_1") (pintype "power_in"))
      (node (ref "C426") (pin "1") (pinfunction "1_1") (pintype "power_in"))
      (node (ref "C427") (pin "1") (pinfunction "1_1") (pintype "power_in"))
      (node (ref "C428") (pin "1") (pinfunction "1_1") (pintype "power_in"))
      (node (ref "C429") (pin "1") (pinfunction "1_1") (pintype "power_in"))
      (node (ref "D25") (pin "20") (pinfunction "Vdd_20") (pintype "passive"))
      (node (ref "D26") (pin "3") (pinfunction "VCC_3") (pintype "passive"))
      (node (ref "D27") (pin "8") (pinfunction "Vcc_8") (pintype "passive"))
      (node (ref "J20") (pin "12") (pinfunction "12_12") (pintype "passive"))
      (node (ref "R264") (pin "2") (pinfunction "2_2") (pintype "passive"))
      (node (ref "R265") (pin "1") (pinfunction "1_1") (pintype "passive"))
      (node (ref "R266") (pin "2") (pinfunction "2_2") (pintype "passive"))
      (node (ref "R267") (pin "2") (pinfunction "2_2") (pintype "passive"))
      (node (ref "R268") (pin "2") (pinfunction "2_2") (pintype "passive"))
      (node (ref "R297") (pin "1") (pinfunction "1_1") (pintype "passive"))
    )
    (net (code "44") (name "/VCC5V0_SYS") (class "Default")
      (node (ref "J20") (pin "13") (pinfunction "13_13") (pintype "passive"))
    )
    (net (code "45") (name "/VCC12V_SYS") (class "Default")
      (node (ref "J20") (pin "14") (pinfunction "14_14") (pintype "passive"))
    )
    (net (code "46") (name "/VCC_3V0") (class "Default")
      (node (ref "R269") (pin "2") (pinfunction "2_2") (pintype "passive"))
      (node (ref "R270") (pin "2") (pinfunction "2_2") (pintype "passive"))
      (node (ref "R277") (pin "2") (pinfunction "2_2") (pintype "passive"))
      (node (ref "R281") (pin "2") (pinfunction "2_2") (pintype "passive"))
    )
    (net (code "47") (name "Net-(D25-OSC1)") (class "Default")
      (node (ref "C424") (pin "1") (pinfunction "1_1") (pintype "power_in"))
      (node (ref "D25") (pin "9") (pinfunction "OSC1_9") (pintype "passive"))
      (node (ref "Z6") (pin "1") (pinfunction "IN/OUT_1") (pintype "bidirectional"))
    )
    (net (code "48") (name "Net-(D25-OSC2)") (class "Default")
      (node (ref "C425") (pin "1") (pinfunction "1_1") (pintype "power_in"))
      (node (ref "D25") (pin "8") (pinfunction "OSC2_8") (pintype "passive"))
      (node (ref "Z6") (pin "3") (pinfunction "IN/OUT_3") (pintype "bidirectional"))
    )
    (net (code "49") (name "Net-(D25-RXCAN)") (class "Default")
      (node (ref "D25") (pin "2") (pinfunction "RXCAN_2") (pintype "passive"))
      (node (ref "D26") (pin "4") (pinfunction "R_4") (pintype "passive"))
    )
    (net (code "50") (name "Net-(D25-TXCAN)") (class "Default")
      (node (ref "D25") (pin "1") (pinfunction "TXCAN_1") (pintype "passive"))
      (node (ref "D26") (pin "1") (pinfunction "D_1") (pintype "passive"))
    )
    (net (code "51") (name "Net-(D25-~{RESET})") (class "Default")
      (node (ref "D25") (pin "19") (pinfunction "~{RESET}_19") (pintype "passive"))
      (node (ref "R264") (pin "1") (pinfunction "1_1") (pintype "passive"))
    )
    (net (code "52") (name "Net-(D25-~{TX0RTS})") (class "Default")
      (node (ref "D25") (pin "4") (pinfunction "~{TX0RTS}_4") (pintype "passive"))
      (node (ref "R266") (pin "1") (pinfunction "1_1") (pintype "passive"))
    )
    (net (code "53") (name "Net-(D25-~{TX1RTS})") (class "Default")
      (node (ref "D25") (pin "5") (pinfunction "~{TX1RTS}_5") (pintype "passive"))
      (node (ref "R267") (pin "1") (pinfunction "1_1") (pintype "passive"))
    )
    (net (code "54") (name "Net-(D25-~{TX2RTS})") (class "Default")
      (node (ref "D25") (pin "7") (pinfunction "~{TX2RTS}_7") (pintype "passive"))
      (node (ref "R268") (pin "1") (pinfunction "1_1") (pintype "passive"))
    )
    (net (code "55") (name "Net-(D26-RS)") (class "Default")
      (node (ref "D26") (pin "8") (pinfunction "RS_8") (pintype "passive"))
      (node (ref "R263") (pin "1") (pinfunction "1_1") (pintype "passive"))
    )
    (net (code "56") (name "Net-(D27-DE)") (class "Default")
      (node (ref "D27") (pin "3") (pinfunction "DE_3") (pintype "passive"))
      (node (ref "R295") (pin "2") (pinfunction "2_2") (pintype "passive"))
    )
    (net (code "57") (name "Net-(D27-DI)") (class "Default")
      (node (ref "D27") (pin "4") (pinfunction "DI_4") (pintype "passive"))
      (node (ref "R296") (pin "2") (pinfunction "2_2") (pintype "passive"))
    )
    (net (code "58") (name "Net-(D27-R)") (class "Default")
      (node (ref "D27") (pin "1") (pinfunction "R_1") (pintype "passive"))
      (node (ref "R292") (pin "2") (pinfunction "2_2") (pintype "passive"))
    )
    (net (code "59") (name "Net-(D27-RE)") (class "Default")
      (node (ref "D27") (pin "2") (pinfunction "RE_2") (pintype "passive"))
      (node (ref "R294") (pin "2") (pinfunction "2_2") (pintype "passive"))
    )
    (net (code "60") (name "Net-(J18-Pad2)") (class "Default")
      (node (ref "J18") (pin "2") (pinfunction "2_2") (pintype "passive"))
      (node (ref "R258") (pin "2") (pinfunction "2_2") (pintype "passive"))
    )
    (net (code "61") (name "Net-(J20-Pad2)") (class "Default")
      (node (ref "J20") (pin "2") (pinfunction "2_2") (pintype "passive"))
      (node (ref "R285") (pin "1") (pinfunction "1_1") (pintype "passive"))
    )
    (net (code "62") (name "Net-(J20-Pad3)") (class "Default")
      (node (ref "J20") (pin "3") (pinfunction "3_3") (pintype "passive"))
      (node (ref "R286") (pin "2") (pinfunction "2_2") (pintype "passive"))
    )
    (net (code "63") (name "Net-(J20-Pad4)") (class "Default")
      (node (ref "J20") (pin "4") (pinfunction "4_4") (pintype "passive"))
      (node (ref "R287") (pin "1") (pinfunction "1_1") (pintype "passive"))
    )
    (net (code "64") (name "Net-(J20-Pad5)") (class "Default")
      (node (ref "J20") (pin "5") (pinfunction "5_5") (pintype "passive"))
      (node (ref "R288") (pin "2") (pinfunction "2_2") (pintype "passive"))
    )
    (net (code "65") (name "Net-(J20-Pad6)") (class "Default")
      (node (ref "J20") (pin "6") (pinfunction "6_6") (pintype "passive"))
      (node (ref "R289") (pin "1") (pinfunction "1_1") (pintype "passive"))
    )
    (net (code "66") (name "Net-(J20-Pad7)") (class "Default")
      (node (ref "J20") (pin "7") (pinfunction "7_7") (pintype "passive"))
      (node (ref "R290") (pin "2") (pinfunction "2_2") (pintype "passive"))
    )
    (net (code "67") (name "Net-(J20-Pad8)") (class "Default")
      (node (ref "J20") (pin "8") (pinfunction "8_8") (pintype "passive"))
      (node (ref "R291") (pin "1") (pinfunction "1_1") (pintype "passive"))
    )
    (net (code "68") (name "Net-(J20-Pad9)") (class "Default")
      (node (ref "J20") (pin "9") (pinfunction "9_9") (pintype "passive"))
      (node (ref "R293") (pin "2") (pinfunction "2_2") (pintype "passive"))
    )
    (net (code "69") (name "Net-(J22-Pad4)") (class "Default")
      (node (ref "J22") (pin "4") (pinfunction "4_4") (pintype "power_in"))
      (node (ref "R297") (pin "2") (pinfunction "2_2") (pintype "passive"))
    )
    (net (code "70") (name "Net-(U2A-A)") (class "Default")
      (node (ref "R271") (pin "1") (pinfunction "1_1") (pintype "passive"))
      (node (ref "R273") (pin "1") (pinfunction "1_1") (pintype "passive"))
      (node (ref "U2") (pin "1") (pinfunction "A_1") (pintype "passive"))
      (node (ref "VD35") (pin "2") (pinfunction "C_2") (pintype "passive"))
    )
    (net (code "71") (name "Net-(U2B-A)") (class "Default")
      (node (ref "R272") (pin "1") (pinfunction "1_1") (pintype "passive"))
      (node (ref "R275") (pin "1") (pinfunction "1_1") (pintype "passive"))
      (node (ref "U2") (pin "3") (pinfunction "A_3") (pintype "passive"))
      (node (ref "VD36") (pin "2") (pinfunction "C_2") (pintype "passive"))
    )
    (net (code "72") (name "Net-(U2C-A)") (class "Default")
      (node (ref "R278") (pin "1") (pinfunction "1_1") (pintype "passive"))
      (node (ref "R279") (pin "1") (pinfunction "1_1") (pintype "passive"))
      (node (ref "U2") (pin "5") (pinfunction "A_5") (pintype "passive"))
      (node (ref "VD39") (pin "2") (pinfunction "C_2") (pintype "passive"))
    )
    (net (code "73") (name "Net-(U2D-A)") (class "Default")
      (node (ref "R282") (pin "1") (pinfunction "1_1") (pintype "passive"))
      (node (ref "R283") (pin "1") (pinfunction "1_1") (pintype "passive"))
      (node (ref "U2") (pin "7") (pinfunction "A_7") (pintype "passive"))
      (node (ref "VD40") (pin "2") (pinfunction "C_2") (pintype "passive"))
    )
    (net (code "74") (name "unconnected-(D25-CLOKOUT{slash}SOF-Pad3)") (class "Default")
      (node (ref "D25") (pin "3") (pinfunction "CLOKOUT/SOF_3") (pintype "passive"))
    )
    (net (code "75") (name "unconnected-(D25-NC-Pad6)") (class "Default")
      (node (ref "D25") (pin "6") (pinfunction "NC_6") (pintype "passive"))
    )
    (net (code "76") (name "unconnected-(D25-NC-Pad15)") (class "Default")
      (node (ref "D25") (pin "15") (pinfunction "NC_15") (pintype "passive"))
    )
    (net (code "77") (name "unconnected-(D25-~{RX0BF}-Pad12)") (class "Default")
      (node (ref "D25") (pin "12") (pinfunction "~{RX0BF}_12") (pintype "passive"))
    )
    (net (code "78") (name "unconnected-(D25-~{RX1BF}-Pad11)") (class "Default")
      (node (ref "D25") (pin "11") (pinfunction "~{RX1BF}_11") (pintype "passive"))
    )
    (net (code "79") (name "unconnected-(D26-Vref-Pad5)") (class "Default")
      (node (ref "D26") (pin "5") (pinfunction "Vref_5") (pintype "passive"))
    )
    (net (code "80") (name "unconnected-(VD37-IN4-Pad5)") (class "Default")
      (node (ref "VD37") (pin "5") (pinfunction "IN4_5") (pintype "passive"))
    )
    (net (code "81") (name "unconnected-(VD38-IN4-Pad5)") (class "Default")
      (node (ref "VD38") (pin "5") (pinfunction "IN4_5") (pintype "passive"))
    )
    (net (code "82") (name "unconnected-(VD41-IN4-Pad5)") (class "Default")
      (node (ref "VD41") (pin "5") (pinfunction "IN4_5") (pintype "passive"))
    )
  )
)
